# Sch.net
KiCad netlist of a schematic drawn in Altium Designer
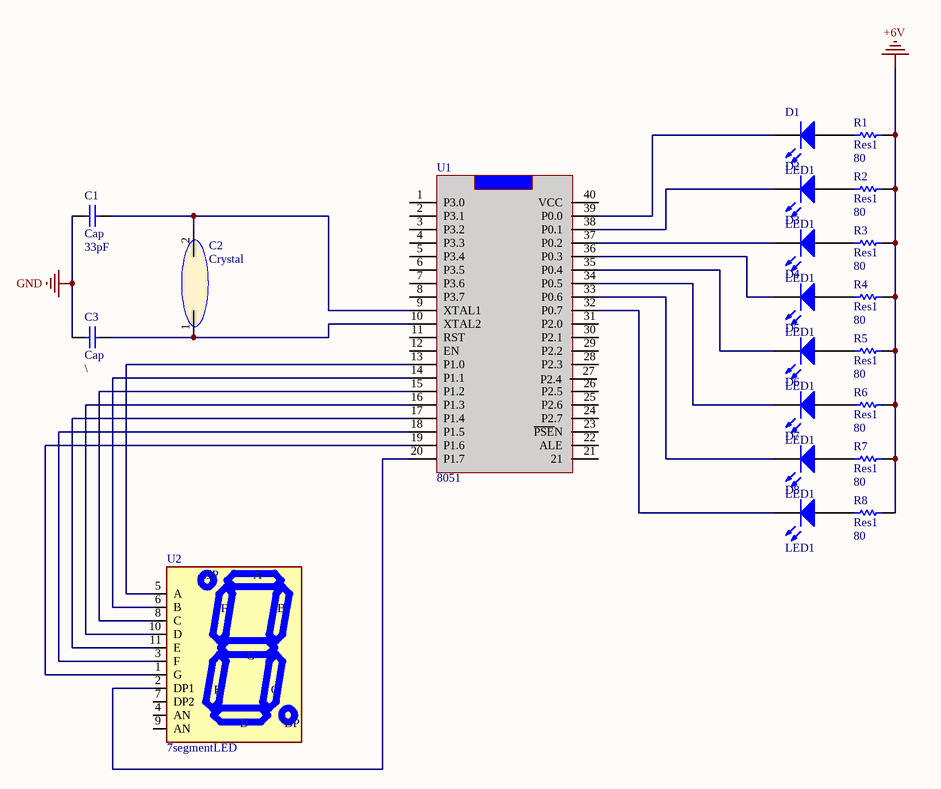
[diagram p0: Sch.SchDoc]

(export (version "E")
  (design (tool "Eeschema 10.0.6"))
  (components
    (comp (ref "C1")
      (value "Cap")
      (footprint "Cap")
      (description "Capacitor")
      (fields (field (name "ALTIUM_VALUE") "33pF") (field (name "PUBLISHER") "Altium Limited"))
      (libsource (lib "Miscellaneous Devices") (part "Cap"))
    )
    (comp (ref "C2") (value "Crystal") (footprint "Crystal") (libsource (lib "Schlib") (part "Crystal")))
    (comp (ref "C3")
      (value "Cap")
      (footprint "Cap")
      (description "Capacitor")
      (fields (field (name "PUBLISHER") "Altium Limited"))
      (libsource (lib "Miscellaneous Devices") (part "Cap"))
    )
    (comp (ref "D1")
      (value "LED1")
      (footprint "LED")
      (description "Typical RED GaAs LED")
      (fields (field (name "PUBLISHER") "Altium Limited"))
      (libsource (lib "Miscellaneous Devices") (part "LED1"))
    )
    (comp (ref "D2")
      (value "LED1")
      (footprint "LED")
      (description "Typical RED GaAs LED")
      (fields (field (name "PUBLISHER") "Altium Limited"))
      (libsource (lib "Miscellaneous Devices") (part "LED1"))
    )
    (comp (ref "D3")
      (value "LED1")
      (footprint "LED")
      (description "Typical RED GaAs LED")
      (fields (field (name "PUBLISHER") "Altium Limited"))
      (libsource (lib "Miscellaneous Devices") (part "LED1"))
    )
    (comp (ref "D4")
      (value "LED1")
      (footprint "LED")
      (description "Typical RED GaAs LED")
      (fields (field (name "PUBLISHER") "Altium Limited"))
      (libsource (lib "Miscellaneous Devices") (part "LED1"))
    )
    (comp (ref "D5")
      (value "LED1")
      (footprint "LED")
      (description "Typical RED GaAs LED")
      (fields (field (name "PUBLISHER") "Altium Limited"))
      (libsource (lib "Miscellaneous Devices") (part "LED1"))
    )
    (comp (ref "D6")
      (value "LED1")
      (footprint "LED")
      (description "Typical RED GaAs LED")
      (fields (field (name "PUBLISHER") "Altium Limited"))
      (libsource (lib "Miscellaneous Devices") (part "LED1"))
    )
    (comp (ref "D7")
      (value "LED1")
      (footprint "LED")
      (description "Typical RED GaAs LED")
      (fields (field (name "PUBLISHER") "Altium Limited"))
      (libsource (lib "Miscellaneous Devices") (part "LED1"))
    )
    (comp (ref "D8")
      (value "LED1")
      (footprint "LED")
      (description "Typical RED GaAs LED")
      (fields (field (name "PUBLISHER") "Altium Limited"))
      (libsource (lib "Miscellaneous Devices") (part "LED1"))
    )
    (comp (ref "R1")
      (value "Res1")
      (footprint "Res")
      (description "Resistor")
      (fields (field (name "ALTIUM_VALUE") "80") (field (name "PUBLISHER") "Altium Limited"))
      (libsource (lib "Miscellaneous Devices") (part "Res1"))
    )
    (comp (ref "R2")
      (value "Res1")
      (footprint "Res")
      (description "Resistor")
      (fields (field (name "ALTIUM_VALUE") "80") (field (name "PUBLISHER") "Altium Limited"))
      (libsource (lib "Miscellaneous Devices") (part "Res1"))
    )
    (comp (ref "R3")
      (value "Res1")
      (footprint "Res")
      (description "Resistor")
      (fields (field (name "ALTIUM_VALUE") "80") (field (name "PUBLISHER") "Altium Limited"))
      (libsource (lib "Miscellaneous Devices") (part "Res1"))
    )
    (comp (ref "R4")
      (value "Res1")
      (footprint "Res")
      (description "Resistor")
      (fields (field (name "ALTIUM_VALUE") "80") (field (name "PUBLISHER") "Altium Limited"))
      (libsource (lib "Miscellaneous Devices") (part "Res1"))
    )
    (comp (ref "R5")
      (value "Res1")
      (footprint "Res")
      (description "Resistor")
      (fields (field (name "ALTIUM_VALUE") "80") (field (name "PUBLISHER") "Altium Limited"))
      (libsource (lib "Miscellaneous Devices") (part "Res1"))
    )
    (comp (ref "R6")
      (value "Res1")
      (footprint "Res")
      (description "Resistor")
      (fields (field (name "ALTIUM_VALUE") "80") (field (name "PUBLISHER") "Altium Limited"))
      (libsource (lib "Miscellaneous Devices") (part "Res1"))
    )
    (comp (ref "R7")
      (value "Res1")
      (footprint "Res")
      (description "Resistor")
      (fields (field (name "ALTIUM_VALUE") "80") (field (name "PUBLISHER") "Altium Limited"))
      (libsource (lib "Miscellaneous Devices") (part "Res1"))
    )
    (comp (ref "R8")
      (value "Res1")
      (footprint "Res")
      (description "Resistor")
      (fields (field (name "ALTIUM_VALUE") "80") (field (name "PUBLISHER") "Altium Limited"))
      (libsource (lib "Miscellaneous Devices") (part "Res1"))
    )
    (comp (ref "U1") (value "8051") (footprint "8051") (libsource (lib "Schlib") (part "8051")))
    (comp (ref "U2")
      (value "7segmentLED")
      (footprint "Display")
      (libsource (lib "Schlib") (part "7segmentLED"))
    )
  )
  (nets
    (net (code "1") (name "+6V") (class "Default")
      (node (ref "R1") (pin "2") (pinfunction "2_2") (pintype "passive"))
      (node (ref "R2") (pin "2") (pinfunction "2_2") (pintype "passive"))
      (node (ref "R3") (pin "2") (pinfunction "2_2") (pintype "passive"))
      (node (ref "R4") (pin "2") (pinfunction "2_2") (pintype "passive"))
      (node (ref "R5") (pin "2") (pinfunction "2_2") (pintype "passive"))
      (node (ref "R6") (pin "2") (pinfunction "2_2") (pintype "passive"))
      (node (ref "R7") (pin "2") (pinfunction "2_2") (pintype "passive"))
      (node (ref "R8") (pin "2") (pinfunction "2_2") (pintype "passive"))
    )
    (net (code "2") (name "GND") (class "Default")
      (node (ref "C1") (pin "1") (pinfunction "1_1") (pintype "passive"))
      (node (ref "C3") (pin "1") (pinfunction "1_1") (pintype "passive"))
    )
    (net (code "3") (name "Net-(D1-A)") (class "Default")
      (node (ref "D1") (pin "1") (pinfunction "A_1") (pintype "passive"))
      (node (ref "R1") (pin "1") (pinfunction "1_1") (pintype "passive"))
    )
    (net (code "4") (name "Net-(D1-K)") (class "Default")
      (node (ref "D1") (pin "2") (pinfunction "K_2") (pintype "passive"))
      (node (ref "U1") (pin "39") (pinfunction "P0.0_39") (pintype "passive"))
    )
    (net (code "5") (name "Net-(D2-A)") (class "Default")
      (node (ref "D2") (pin "1") (pinfunction "A_1") (pintype "passive"))
      (node (ref "R2") (pin "1") (pinfunction "1_1") (pintype "passive"))
    )
    (net (code "6") (name "Net-(D2-K)") (class "Default")
      (node (ref "D2") (pin "2") (pinfunction "K_2") (pintype "passive"))
      (node (ref "U1") (pin "38") (pinfunction "P0.1_38") (pintype "passive"))
    )
    (net (code "7") (name "Net-(D3-A)") (class "Default")
      (node (ref "D3") (pin "1") (pinfunction "A_1") (pintype "passive"))
      (node (ref "R3") (pin "1") (pinfunction "1_1") (pintype "passive"))
    )
    (net (code "8") (name "Net-(D3-K)") (class "Default")
      (node (ref "D3") (pin "2") (pinfunction "K_2") (pintype "passive"))
      (node (ref "U1") (pin "37") (pinfunction "P0.2_37") (pintype "passive"))
    )
    (net (code "9") (name "Net-(D4-A)") (class "Default")
      (node (ref "D4") (pin "1") (pinfunction "A_1") (pintype "passive"))
      (node (ref "R4") (pin "1") (pinfunction "1_1") (pintype "passive"))
    )
    (net (code "10") (name "Net-(D4-K)") (class "Default")
      (node (ref "D4") (pin "2") (pinfunction "K_2") (pintype "passive"))
      (node (ref "U1") (pin "36") (pinfunction "P0.3_36") (pintype "passive"))
    )
    (net (code "11") (name "Net-(D5-A)") (class "Default")
      (node (ref "D5") (pin "1") (pinfunction "A_1") (pintype "passive"))
      (node (ref "R5") (pin "1") (pinfunction "1_1") (pintype "passive"))
    )
    (net (code "12") (name "Net-(D5-K)") (class "Default")
      (node (ref "D5") (pin "2") (pinfunction "K_2") (pintype "passive"))
      (node (ref "U1") (pin "35") (pinfunction "P0.4_35") (pintype "passive"))
    )
    (net (code "13") (name "Net-(D6-A)") (class "Default")
      (node (ref "D6") (pin "1") (pinfunction "A_1") (pintype "passive"))
      (node (ref "R6") (pin "1") (pinfunction "1_1") (pintype "passive"))
    )
    (net (code "14") (name "Net-(D6-K)") (class "Default")
      (node (ref "D6") (pin "2") (pinfunction "K_2") (pintype "passive"))
      (node (ref "U1") (pin "34") (pinfunction "P0.5_34") (pintype "passive"))
    )
    (net (code "15") (name "Net-(D7-A)") (class "Default")
      (node (ref "D7") (pin "1") (pinfunction "A_1") (pintype "passive"))
      (node (ref "R7") (pin "1") (pinfunction "1_1") (pintype "passive"))
    )
    (net (code "16") (name "Net-(D7-K)") (class "Default")
      (node (ref "D7") (pin "2") (pinfunction "K_2") (pintype "passive"))
      (node (ref "U1") (pin "33") (pinfunction "P0.6_33") (pintype "passive"))
    )
    (net (code "17") (name "Net-(D8-A)") (class "Default")
      (node (ref "D8") (pin "1") (pinfunction "A_1") (pintype "passive"))
      (node (ref "R8") (pin "1") (pinfunction "1_1") (pintype "passive"))
    )
    (net (code "18") (name "Net-(D8-K)") (class "Default")
      (node (ref "D8") (pin "2") (pinfunction "K_2") (pintype "passive"))
      (node (ref "U1") (pin "32") (pinfunction "P0.7_32") (pintype "passive"))
    )
    (net (code "19") (name "Net-(U1-P1.0)") (class "Default")
      (node (ref "U1") (pin "13") (pinfunction "P1.0_13") (pintype "passive"))
      (node (ref "U2") (pin "5") (pinfunction "A_5") (pintype "passive"))
    )
    (net (code "20") (name "Net-(U1-P1.1)") (class "Default")
      (node (ref "U1") (pin "14") (pinfunction "P1.1_14") (pintype "passive"))
      (node (ref "U2") (pin "6") (pinfunction "B_6") (pintype "passive"))
    )
    (net (code "21") (name "Net-(U1-P1.2)") (class "Default")
      (node (ref "U1") (pin "15") (pinfunction "P1.2_15") (pintype "passive"))
      (node (ref "U2") (pin "8") (pinfunction "C_8") (pintype "passive"))
    )
    (net (code "22") (name "Net-(U1-P1.3)") (class "Default")
      (node (ref "U1") (pin "16") (pinfunction "P1.3_16") (pintype "passive"))
      (node (ref "U2") (pin "10") (pinfunction "D_10") (pintype "passive"))
    )
    (net (code "23") (name "Net-(U1-P1.4)") (class "Default")
      (node (ref "U1") (pin "17") (pinfunction "P1.4_17") (pintype "passive"))
      (node (ref "U2") (pin "11") (pinfunction "E_11") (pintype "passive"))
    )
    (net (code "24") (name "Net-(U1-P1.5)") (class "Default")
      (node (ref "U1") (pin "18") (pinfunction "P1.5_18") (pintype "passive"))
      (node (ref "U2") (pin "3") (pinfunction "F_3") (pintype "passive"))
    )
    (net (code "25") (name "Net-(U1-P1.6)") (class "Default")
      (node (ref "U1") (pin "19") (pinfunction "P1.6_19") (pintype "passive"))
      (node (ref "U2") (pin "1") (pinfunction "G_1") (pintype "passive"))
    )
    (net (code "26") (name "Net-(U1-P1.7)") (class "Default")
      (node (ref "U1") (pin "20") (pinfunction "P1.7_20") (pintype "passive"))
      (node (ref "U2") (pin "2") (pinfunction "DP1_2") (pintype "passive"))
    )
    (net (code "27") (name "Net-(U1-XTAL1)") (class "Default")
      (node (ref "C1") (pin "2") (pinfunction "2_2") (pintype "passive"))
      (node (ref "C2") (pin "2") (pinfunction "2_2") (pintype "passive"))
      (node (ref "U1") (pin "9") (pinfunction "XTAL1_9") (pintype "passive"))
    )
    (net (code "28") (name "Net-(U1-XTAL2)") (class "Default")
      (node (ref "C2") (pin "1") (pinfunction "1_1") (pintype "passive"))
      (node (ref "C3") (pin "2") (pinfunction "2_2") (pintype "passive"))
      (node (ref "U1") (pin "10") (pinfunction "XTAL2_10") (pintype "passive"))
    )
    (net (code "29") (name "unconnected-(U1-ALE-Pad22)") (class "Default")
      (node (ref "U1") (pin "22") (pinfunction "ALE_22") (pintype "passive"))
    )
    (net (code "30") (name "unconnected-(U1-EN-Pad12)") (class "Default")
      (node (ref "U1") (pin "12") (pinfunction "EN_12") (pintype "passive"))
    )
    (net (code "31") (name "unconnected-(U1-P2.0-Pad31)") (class "Default")
      (node (ref "U1") (pin "31") (pinfunction "P2.0_31") (pintype "passive"))
    )
    (net (code "32") (name "unconnected-(U1-P2.1-Pad30)") (class "Default")
      (node (ref "U1") (pin "30") (pinfunction "P2.1_30") (pintype "passive"))
    )
    (net (code "33") (name "unconnected-(U1-P2.2-Pad29)") (class "Default")
      (node (ref "U1") (pin "29") (pinfunction "P2.2_29") (pintype "passive"))
    )
    (net (code "34") (name "unconnected-(U1-P2.3-Pad28)") (class "Default")
      (node (ref "U1") (pin "28") (pinfunction "P2.3_28") (pintype "passive"))
    )
    (net (code "35") (name "unconnected-(U1-P2.4-Pad27)") (class "Default")
      (node (ref "U1") (pin "27") (pinfunction "P2.4_27") (pintype "passive"))
    )
    (net (code "36") (name "unconnected-(U1-P2.5-Pad26)") (class "Default")
      (node (ref "U1") (pin "26") (pinfunction "P2.5_26") (pintype "passive"))
    )
    (net (code "37") (name "unconnected-(U1-P2.6-Pad25)") (class "Default")
      (node (ref "U1") (pin "25") (pinfunction "P2.6_25") (pintype "passive"))
    )
    (net (code "38") (name "unconnected-(U1-P2.7-Pad24)") (class "Default")
      (node (ref "U1") (pin "24") (pinfunction "P2.7_24") (pintype "passive"))
    )
    (net (code "39") (name "unconnected-(U1-P3.0-Pad1)") (class "Default")
      (node (ref "U1") (pin "1") (pinfunction "P3.0_1") (pintype "passive"))
    )
    (net (code "40") (name "unconnected-(U1-P3.1-Pad2)") (class "Default")
      (node (ref "U1") (pin "2") (pinfunction "P3.1_2") (pintype "passive"))
    )
    (net (code "41") (name "unconnected-(U1-P3.2-Pad3)") (class "Default")
      (node (ref "U1") (pin "3") (pinfunction "P3.2_3") (pintype "passive"))
    )
    (net (code "42") (name "unconnected-(U1-P3.3-Pad4)") (class "Default")
      (node (ref "U1") (pin "4") (pinfunction "P3.3_4") (pintype "passive"))
    )
    (net (code "43") (name "unconnected-(U1-P3.4-Pad5)") (class "Default")
      (node (ref "U1") (pin "5") (pinfunction "P3.4_5") (pintype "passive"))
    )
    (net (code "44") (name "unconnected-(U1-P3.5-Pad6)") (class "Default")
      (node (ref "U1") (pin "6") (pinfunction "P3.5_6") (pintype "passive"))
    )
    (net (code "45") (name "unconnected-(U1-P3.6-Pad7)") (class "Default")
      (node (ref "U1") (pin "7") (pinfunction "P3.6_7") (pintype "passive"))
    )
    (net (code "46") (name "unconnected-(U1-P3.7-Pad8)") (class "Default")
      (node (ref "U1") (pin "8") (pinfunction "P3.7_8") (pintype "passive"))
    )
    (net (code "47") (name "unconnected-(U1-Pad21)") (class "Default")
      (node (ref "U1") (pin "21") (pinfunction "21_21") (pintype "passive"))
    )
    (net (code "48") (name "unconnected-(U1-RST-Pad11)") (class "Default")
      (node (ref "U1") (pin "11") (pinfunction "RST_11") (pintype "passive"))
    )
    (net (code "49") (name "unconnected-(U1-VCC-Pad40)") (class "Default")
      (node (ref "U1") (pin "40") (pinfunction "VCC_40") (pintype "passive"))
    )
    (net (code "50") (name "unconnected-(U1-~{PSE}N-Pad23)") (class "Default")
      (node (ref "U1") (pin "23") (pinfunction "~{PSE}N_23") (pintype "passive"))
    )
    (net (code "51") (name "unconnected-(U2-AN-Pad4)") (class "Default")
      (node (ref "U2") (pin "4") (pinfunction "AN_4") (pintype "passive"))
    )
    (net (code "52") (name "unconnected-(U2-AN-Pad9)") (class "Default")
      (node (ref "U2") (pin "9") (pinfunction "AN_9") (pintype "passive"))
    )
    (net (code "53") (name "unconnected-(U2-DP2-Pad7)") (class "Default")
      (node (ref "U2") (pin "7") (pinfunction "DP2_7") (pintype "passive"))
    )
  )
)
